# MSPBreakout.net
KiCad netlist of a schematic drawn in Altium Designer
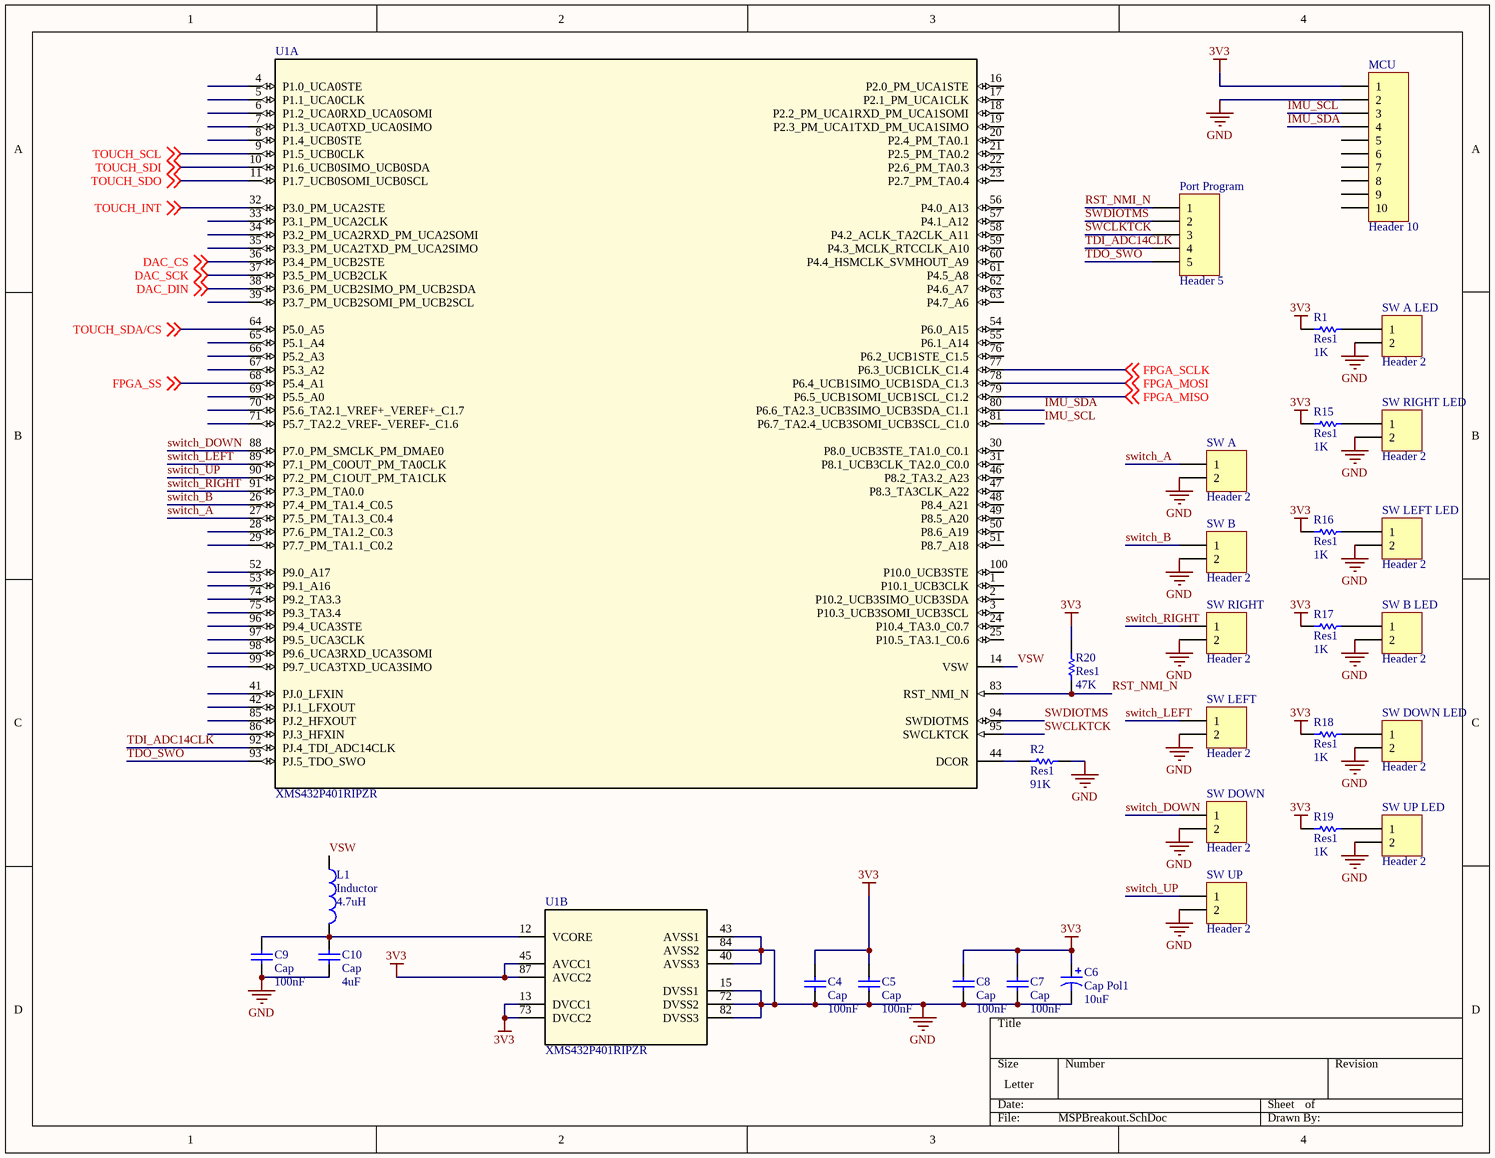
[diagram p0: MSPBreakout.SchDoc]

(export (version "E")
  (design (tool "Eeschema 10.0.6"))
  (components
    (comp (ref "C4")
      (value "Cap")
      (footprint "6-0805_M")
      (description "Capacitor")
      (fields (field (name "ALTIUM_VALUE") "100nF") (field (name "PUBLISHER") "Altium Limited"))
      (libsource (lib "Miscellaneous Devices") (part "Cap"))
    )
    (comp (ref "C5")
      (value "Cap")
      (footprint "6-0805_M")
      (description "Capacitor")
      (fields (field (name "ALTIUM_VALUE") "100nF") (field (name "PUBLISHER") "Altium Limited"))
      (libsource (lib "Miscellaneous Devices") (part "Cap"))
    )
    (comp (ref "C6")
      (value "Cap Pol1")
      (footprint "6-0805_M")
      (description "Polarized Capacitor (Radial)")
      (fields (field (name "ALTIUM_VALUE") "10uF") (field (name "PUBLISHER") "Altium Limited"))
      (libsource (lib "Miscellaneous Devices") (part "Cap Pol1"))
    )
    (comp (ref "C7")
      (value "Cap")
      (footprint "6-0805_M")
      (description "Capacitor")
      (fields (field (name "ALTIUM_VALUE") "100nF") (field (name "PUBLISHER") "Altium Limited"))
      (libsource (lib "Miscellaneous Devices") (part "Cap"))
    )
    (comp (ref "C8")
      (value "Cap")
      (footprint "6-0805_M")
      (description "Capacitor")
      (fields (field (name "ALTIUM_VALUE") "100nF") (field (name "PUBLISHER") "Altium Limited"))
      (libsource (lib "Miscellaneous Devices") (part "Cap"))
    )
    (comp (ref "C9")
      (value "Cap")
      (footprint "6-0805_M")
      (description "Capacitor")
      (fields (field (name "ALTIUM_VALUE") "100nF") (field (name "PUBLISHER") "Altium Limited"))
      (libsource (lib "Miscellaneous Devices") (part "Cap"))
    )
    (comp (ref "C10")
      (value "Cap")
      (footprint "6-0805_M")
      (description "Capacitor")
      (fields (field (name "ALTIUM_VALUE") "4uF") (field (name "PUBLISHER") "Altium Limited"))
      (libsource (lib "Miscellaneous Devices") (part "Cap"))
    )
    (comp (ref "L1")
      (value "Inductor")
      (footprint "AXIAL-0.3")
      (fields (field (name "ALTIUM_VALUE") "4.7uH") (field (name "PUBLISHER") "Altium Limited"))
      (libsource (lib "Miscellaneous Devices") (part "Inductor"))
    )
    (comp (ref "MCU")
      (value "Header 10")
      (footprint "HDR1X10")
      (description "Header, 10-Pin")
      (fields (field (name "PUBLISHER") "Altium Limited"))
      (libsource (lib "Miscellaneous Connectors") (part "Header 10"))
    )
    (comp (ref "Port Program")
      (value "Header 5")
      (footprint "HDR1X5")
      (description "Header, 5-Pin")
      (fields (field (name "PUBLISHER") "Altium Limited"))
      (libsource (lib "Miscellaneous Connectors") (part "Header 5"))
    )
    (comp (ref "R1")
      (value "Res1")
      (footprint "6-0805_M")
      (description "Resistor")
      (fields (field (name "ALTIUM_VALUE") "1K") (field (name "PUBLISHER") "Altium Limited"))
      (libsource (lib "Miscellaneous Devices") (part "Res1"))
    )
    (comp (ref "R2")
      (value "Res1")
      (footprint "6-0805_M")
      (description "Resistor")
      (fields (field (name "ALTIUM_VALUE") "91K") (field (name "PUBLISHER") "Altium Limited"))
      (libsource (lib "Miscellaneous Devices") (part "Res1"))
    )
    (comp (ref "R15")
      (value "Res1")
      (footprint "6-0805_M")
      (description "Resistor")
      (fields (field (name "ALTIUM_VALUE") "1K") (field (name "PUBLISHER") "Altium Limited"))
      (libsource (lib "Miscellaneous Devices") (part "Res1"))
    )
    (comp (ref "R16")
      (value "Res1")
      (footprint "6-0805_M")
      (description "Resistor")
      (fields (field (name "ALTIUM_VALUE") "1K") (field (name "PUBLISHER") "Altium Limited"))
      (libsource (lib "Miscellaneous Devices") (part "Res1"))
    )
    (comp (ref "R17")
      (value "Res1")
      (footprint "6-0805_M")
      (description "Resistor")
      (fields (field (name "ALTIUM_VALUE") "1K") (field (name "PUBLISHER") "Altium Limited"))
      (libsource (lib "Miscellaneous Devices") (part "Res1"))
    )
    (comp (ref "R18")
      (value "Res1")
      (footprint "6-0805_M")
      (description "Resistor")
      (fields (field (name "ALTIUM_VALUE") "1K") (field (name "PUBLISHER") "Altium Limited"))
      (libsource (lib "Miscellaneous Devices") (part "Res1"))
    )
    (comp (ref "R19")
      (value "Res1")
      (footprint "6-0805_M")
      (description "Resistor")
      (fields (field (name "ALTIUM_VALUE") "1K") (field (name "PUBLISHER") "Altium Limited"))
      (libsource (lib "Miscellaneous Devices") (part "Res1"))
    )
    (comp (ref "R20")
      (value "Res1")
      (footprint "6-0805_M")
      (description "Resistor")
      (fields (field (name "ALTIUM_VALUE") "47K") (field (name "PUBLISHER") "Altium Limited"))
      (libsource (lib "Miscellaneous Devices") (part "Res1"))
    )
    (comp (ref "SW A")
      (value "Header 2")
      (footprint "HDR1X2")
      (description "Header, 2-Pin")
      (fields (field (name "PUBLISHER") "Altium Limited"))
      (libsource (lib "Miscellaneous Connectors") (part "Header 2"))
    )
    (comp (ref "SW A LED")
      (value "Header 2")
      (footprint "HDR1X2")
      (description "Header, 2-Pin")
      (fields (field (name "PUBLISHER") "Altium Limited"))
      (libsource (lib "Miscellaneous Connectors") (part "Header 2"))
    )
    (comp (ref "SW B")
      (value "Header 2")
      (footprint "HDR1X2")
      (description "Header, 2-Pin")
      (fields (field (name "PUBLISHER") "Altium Limited"))
      (libsource (lib "Miscellaneous Connectors") (part "Header 2"))
    )
    (comp (ref "SW B LED")
      (value "Header 2")
      (footprint "HDR1X2")
      (description "Header, 2-Pin")
      (fields (field (name "PUBLISHER") "Altium Limited"))
      (libsource (lib "Miscellaneous Connectors") (part "Header 2"))
    )
    (comp (ref "SW DOWN")
      (value "Header 2")
      (footprint "HDR1X2")
      (description "Header, 2-Pin")
      (fields (field (name "PUBLISHER") "Altium Limited"))
      (libsource (lib "Miscellaneous Connectors") (part "Header 2"))
    )
    (comp (ref "SW DOWN LED")
      (value "Header 2")
      (footprint "HDR1X2")
      (description "Header, 2-Pin")
      (fields (field (name "PUBLISHER") "Altium Limited"))
      (libsource (lib "Miscellaneous Connectors") (part "Header 2"))
    )
    (comp (ref "SW LEFT")
      (value "Header 2")
      (footprint "HDR1X2")
      (description "Header, 2-Pin")
      (fields (field (name "PUBLISHER") "Altium Limited"))
      (libsource (lib "Miscellaneous Connectors") (part "Header 2"))
    )
    (comp (ref "SW LEFT LED")
      (value "Header 2")
      (footprint "HDR1X2")
      (description "Header, 2-Pin")
      (fields (field (name "PUBLISHER") "Altium Limited"))
      (libsource (lib "Miscellaneous Connectors") (part "Header 2"))
    )
    (comp (ref "SW RIGHT")
      (value "Header 2")
      (footprint "HDR1X2")
      (description "Header, 2-Pin")
      (fields (field (name "PUBLISHER") "Altium Limited"))
      (libsource (lib "Miscellaneous Connectors") (part "Header 2"))
    )
    (comp (ref "SW RIGHT LED")
      (value "Header 2")
      (footprint "HDR1X2")
      (description "Header, 2-Pin")
      (fields (field (name "PUBLISHER") "Altium Limited"))
      (libsource (lib "Miscellaneous Connectors") (part "Header 2"))
    )
    (comp (ref "SW UP")
      (value "Header 2")
      (footprint "HDR1X2")
      (description "Header, 2-Pin")
      (fields (field (name "PUBLISHER") "Altium Limited"))
      (libsource (lib "Miscellaneous Connectors") (part "Header 2"))
    )
    (comp (ref "SW UP LED")
      (value "Header 2")
      (footprint "HDR1X2")
      (description "Header, 2-Pin")
      (fields (field (name "PUBLISHER") "Altium Limited"))
      (libsource (lib "Miscellaneous Connectors") (part "Header 2"))
    )
    (comp (ref "U1")
      (value "XMS432P401RIPZR")
      (footprint "PZ0100A_M")
      (description "Imported")
      (fields (field (name "MANUFACTURER") "Texas Instruments"))
      (libsource (lib "2019-02-10_17-24-31") (part "XMS432P401RIPZR"))
    )
  )
  (nets
    (net (code "1") (name "/IMU_SCL") (class "Default")
      (node (ref "MCU") (pin "3") (pinfunction "3_3") (pintype "passive"))
      (node (ref "U1") (pin "81") (pinfunction "P6.7_TA2.4_UCB3SOMI_UCB3SCL_C1.0_81") (pintype "bidirectional"))
    )
    (net (code "2") (name "/IMU_SDA") (class "Default")
      (node (ref "MCU") (pin "4") (pinfunction "4_4") (pintype "passive"))
      (node (ref "U1") (pin "80") (pinfunction "P6.6_TA2.3_UCB3SIMO_UCB3SDA_C1.1_80") (pintype "bidirectional"))
    )
    (net (code "3") (name "/RST_NMI_N") (class "Default")
      (node (ref "Port Program") (pin "1") (pinfunction "1_1") (pintype "passive"))
      (node (ref "R20") (pin "1") (pinfunction "1_1") (pintype "passive"))
      (node (ref "U1") (pin "83") (pinfunction "RST_NMI_N_83") (pintype "input"))
    )
    (net (code "4") (name "/SWCLKTCK") (class "Default")
      (node (ref "Port Program") (pin "3") (pinfunction "3_3") (pintype "passive"))
      (node (ref "U1") (pin "95") (pinfunction "SWCLKTCK_95") (pintype "input"))
    )
    (net (code "5") (name "/SWDIOTMS") (class "Default")
      (node (ref "Port Program") (pin "2") (pinfunction "2_2") (pintype "passive"))
      (node (ref "U1") (pin "94") (pinfunction "SWDIOTMS_94") (pintype "bidirectional"))
    )
    (net (code "6") (name "/TDI_ADC14CLK") (class "Default")
      (node (ref "Port Program") (pin "4") (pinfunction "4_4") (pintype "passive"))
      (node (ref "U1") (pin "92") (pinfunction "PJ.4_TDI_ADC14CLK_92") (pintype "bidirectional"))
    )
    (net (code "7") (name "/TDO_SWO") (class "Default")
      (node (ref "Port Program") (pin "5") (pinfunction "5_5") (pintype "passive"))
      (node (ref "U1") (pin "93") (pinfunction "PJ.5_TDO_SWO_93") (pintype "bidirectional"))
    )
    (net (code "8") (name "/VSW") (class "Default")
      (node (ref "L1") (pin "1") (pinfunction "1_1") (pintype "passive"))
      (node (ref "U1") (pin "14") (pinfunction "VSW_14") (pintype "passive"))
    )
    (net (code "9") (name "/switch_A") (class "Default")
      (node (ref "SW A") (pin "1") (pinfunction "1_1") (pintype "passive"))
      (node (ref "U1") (pin "27") (pinfunction "P7.5_PM_TA1.3_C0.4_27") (pintype "bidirectional"))
    )
    (net (code "10") (name "/switch_B") (class "Default")
      (node (ref "SW B") (pin "1") (pinfunction "1_1") (pintype "passive"))
      (node (ref "U1") (pin "26") (pinfunction "P7.4_PM_TA1.4_C0.5_26") (pintype "bidirectional"))
    )
    (net (code "11") (name "/switch_DOWN") (class "Default")
      (node (ref "SW DOWN") (pin "1") (pinfunction "1_1") (pintype "passive"))
      (node (ref "U1") (pin "88") (pinfunction "P7.0_PM_SMCLK_PM_DMAE0_88") (pintype "bidirectional"))
    )
    (net (code "12") (name "/switch_LEFT") (class "Default")
      (node (ref "SW LEFT") (pin "1") (pinfunction "1_1") (pintype "passive"))
      (node (ref "U1") (pin "89") (pinfunction "P7.1_PM_C0OUT_PM_TA0CLK_89") (pintype "bidirectional"))
    )
    (net (code "13") (name "/switch_RIGHT") (class "Default")
      (node (ref "SW RIGHT") (pin "1") (pinfunction "1_1") (pintype "passive"))
      (node (ref "U1") (pin "91") (pinfunction "P7.3_PM_TA0.0_91") (pintype "bidirectional"))
    )
    (net (code "14") (name "/switch_UP") (class "Default")
      (node (ref "SW UP") (pin "1") (pinfunction "1_1") (pintype "passive"))
      (node (ref "U1") (pin "90") (pinfunction "P7.2_PM_C1OUT_PM_TA1CLK_90") (pintype "bidirectional"))
    )
    (net (code "15") (name "3V3") (class "Default")
      (node (ref "C4") (pin "2") (pinfunction "2_2") (pintype "passive"))
      (node (ref "C5") (pin "2") (pinfunction "2_2") (pintype "passive"))
      (node (ref "C6") (pin "1") (pinfunction "1_1") (pintype "passive"))
      (node (ref "C7") (pin "2") (pinfunction "2_2") (pintype "passive"))
      (node (ref "C8") (pin "2") (pinfunction "2_2") (pintype "passive"))
      (node (ref "MCU") (pin "1") (pinfunction "1_1") (pintype "passive"))
      (node (ref "R1") (pin "1") (pinfunction "1_1") (pintype "passive"))
      (node (ref "R15") (pin "1") (pinfunction "1_1") (pintype "passive"))
      (node (ref "R16") (pin "1") (pinfunction "1_1") (pintype "passive"))
      (node (ref "R17") (pin "1") (pinfunction "1_1") (pintype "passive"))
      (node (ref "R18") (pin "1") (pinfunction "1_1") (pintype "passive"))
      (node (ref "R19") (pin "1") (pinfunction "1_1") (pintype "passive"))
      (node (ref "R20") (pin "2") (pinfunction "2_2") (pintype "passive"))
      (node (ref "U1") (pin "13") (pinfunction "DVCC1_13") (pintype "power_in"))
      (node (ref "U1") (pin "45") (pinfunction "AVCC1_45") (pintype "power_in"))
      (node (ref "U1") (pin "73") (pinfunction "DVCC2_73") (pintype "power_in"))
      (node (ref "U1") (pin "87") (pinfunction "AVCC2_87") (pintype "power_in"))
    )
    (net (code "16") (name "DAC_CS") (class "Default")
      (node (ref "U1") (pin "36") (pinfunction "P3.4_PM_UCB2STE_36") (pintype "bidirectional"))
    )
    (net (code "17") (name "DAC_DIN") (class "Default")
      (node (ref "U1") (pin "38") (pinfunction "P3.6_PM_UCB2SIMO_PM_UCB2SDA_38") (pintype "bidirectional"))
    )
    (net (code "18") (name "DAC_SCK") (class "Default")
      (node (ref "U1") (pin "37") (pinfunction "P3.5_PM_UCB2CLK_37") (pintype "bidirectional"))
    )
    (net (code "19") (name "FPGA_MISO") (class "Default")
      (node (ref "U1") (pin "79") (pinfunction "P6.5_UCB1SOMI_UCB1SCL_C1.2_79") (pintype "bidirectional"))
    )
    (net (code "20") (name "FPGA_MOSI") (class "Default")
      (node (ref "U1") (pin "78") (pinfunction "P6.4_UCB1SIMO_UCB1SDA_C1.3_78") (pintype "bidirectional"))
    )
    (net (code "21") (name "FPGA_SCLK") (class "Default")
      (node (ref "U1") (pin "77") (pinfunction "P6.3_UCB1CLK_C1.4_77") (pintype "bidirectional"))
    )
    (net (code "22") (name "FPGA_SS") (class "Default")
      (node (ref "U1") (pin "68") (pinfunction "P5.4_A1_68") (pintype "bidirectional"))
    )
    (net (code "23") (name "GND") (class "Default")
      (node (ref "C10") (pin "1") (pinfunction "1_1") (pintype "passive"))
      (node (ref "C4") (pin "1") (pinfunction "1_1") (pintype "passive"))
      (node (ref "C5") (pin "1") (pinfunction "1_1") (pintype "passive"))
      (node (ref "C6") (pin "2") (pinfunction "2_2") (pintype "passive"))
      (node (ref "C7") (pin "1") (pinfunction "1_1") (pintype "passive"))
      (node (ref "C8") (pin "1") (pinfunction "1_1") (pintype "passive"))
      (node (ref "C9") (pin "1") (pinfunction "1_1") (pintype "passive"))
      (node (ref "MCU") (pin "2") (pinfunction "2_2") (pintype "passive"))
      (node (ref "R2") (pin "2") (pinfunction "2_2") (pintype "passive"))
      (node (ref "SW A") (pin "2") (pinfunction "2_2") (pintype "passive"))
      (node (ref "SW A LED") (pin "2") (pinfunction "2_2") (pintype "passive"))
      (node (ref "SW B") (pin "2") (pinfunction "2_2") (pintype "passive"))
      (node (ref "SW B LED") (pin "2") (pinfunction "2_2") (pintype "passive"))
      (node (ref "SW DOWN") (pin "2") (pinfunction "2_2") (pintype "passive"))
      (node (ref "SW DOWN LED") (pin "2") (pinfunction "2_2") (pintype "passive"))
      (node (ref "SW LEFT") (pin "2") (pinfunction "2_2") (pintype "passive"))
      (node (ref "SW LEFT LED") (pin "2") (pinfunction "2_2") (pintype "passive"))
      (node (ref "SW RIGHT") (pin "2") (pinfunction "2_2") (pintype "passive"))
      (node (ref "SW RIGHT LED") (pin "2") (pinfunction "2_2") (pintype "passive"))
      (node (ref "SW UP") (pin "2") (pinfunction "2_2") (pintype "passive"))
      (node (ref "SW UP LED") (pin "2") (pinfunction "2_2") (pintype "passive"))
      (node (ref "U1") (pin "15") (pinfunction "DVSS1_15") (pintype "power_in"))
      (node (ref "U1") (pin "40") (pinfunction "AVSS3_40") (pintype "power_in"))
      (node (ref "U1") (pin "43") (pinfunction "AVSS1_43") (pintype "power_in"))
      (node (ref "U1") (pin "72") (pinfunction "DVSS2_72") (pintype "power_in"))
      (node (ref "U1") (pin "82") (pinfunction "DVSS3_82") (pintype "power_in"))
      (node (ref "U1") (pin "84") (pinfunction "AVSS2_84") (pintype "power_in"))
    )
    (net (code "24") (name "Net-(R1-Pad2)") (class "Default")
      (node (ref "R1") (pin "2") (pinfunction "2_2") (pintype "passive"))
      (node (ref "SW A LED") (pin "1") (pinfunction "1_1") (pintype "passive"))
    )
    (net (code "25") (name "Net-(R15-Pad2)") (class "Default")
      (node (ref "R15") (pin "2") (pinfunction "2_2") (pintype "passive"))
      (node (ref "SW RIGHT LED") (pin "1") (pinfunction "1_1") (pintype "passive"))
    )
    (net (code "26") (name "Net-(R16-Pad2)") (class "Default")
      (node (ref "R16") (pin "2") (pinfunction "2_2") (pintype "passive"))
      (node (ref "SW LEFT LED") (pin "1") (pinfunction "1_1") (pintype "passive"))
    )
    (net (code "27") (name "Net-(R17-Pad2)") (class "Default")
      (node (ref "R17") (pin "2") (pinfunction "2_2") (pintype "passive"))
      (node (ref "SW B LED") (pin "1") (pinfunction "1_1") (pintype "passive"))
    )
    (net (code "28") (name "Net-(R18-Pad2)") (class "Default")
      (node (ref "R18") (pin "2") (pinfunction "2_2") (pintype "passive"))
      (node (ref "SW DOWN LED") (pin "1") (pinfunction "1_1") (pintype "passive"))
    )
    (net (code "29") (name "Net-(R19-Pad2)") (class "Default")
      (node (ref "R19") (pin "2") (pinfunction "2_2") (pintype "passive"))
      (node (ref "SW UP LED") (pin "1") (pinfunction "1_1") (pintype "passive"))
    )
    (net (code "30") (name "Net-(U1A-DCOR)") (class "Default")
      (node (ref "R2") (pin "1") (pinfunction "1_1") (pintype "passive"))
      (node (ref "U1") (pin "44") (pinfunction "DCOR_44") (pintype "passive"))
    )
    (net (code "31") (name "Net-(U1B-VCORE)") (class "Default")
      (node (ref "C10") (pin "2") (pinfunction "2_2") (pintype "passive"))
      (node (ref "C9") (pin "2") (pinfunction "2_2") (pintype "passive"))
      (node (ref "L1") (pin "2") (pinfunction "2_2") (pintype "passive"))
      (node (ref "U1") (pin "12") (pinfunction "VCORE_12") (pintype "power_in"))
    )
    (net (code "32") (name "TOUCH_INT") (class "Default")
      (node (ref "U1") (pin "32") (pinfunction "P3.0_PM_UCA2STE_32") (pintype "bidirectional"))
    )
    (net (code "33") (name "TOUCH_SCL") (class "Default")
      (node (ref "U1") (pin "9") (pinfunction "P1.5_UCB0CLK_9") (pintype "bidirectional"))
    )
    (net (code "34") (name "TOUCH_SDA{slash}CS") (class "Default")
      (node (ref "U1") (pin "64") (pinfunction "P5.0_A5_64") (pintype "bidirectional"))
    )
    (net (code "35") (name "TOUCH_SDI") (class "Default")
      (node (ref "U1") (pin "10") (pinfunction "P1.6_UCB0SIMO_UCB0SDA_10") (pintype "bidirectional"))
    )
    (net (code "36") (name "TOUCH_SDO") (class "Default")
      (node (ref "U1") (pin "11") (pinfunction "P1.7_UCB0SOMI_UCB0SCL_11") (pintype "bidirectional"))
    )
    (net (code "37") (name "unconnected-(MCU-Pad5)") (class "Default")
      (node (ref "MCU") (pin "5") (pinfunction "5_5") (pintype "passive"))
    )
    (net (code "38") (name "unconnected-(MCU-Pad6)") (class "Default")
      (node (ref "MCU") (pin "6") (pinfunction "6_6") (pintype "passive"))
    )
    (net (code "39") (name "unconnected-(MCU-Pad7)") (class "Default")
      (node (ref "MCU") (pin "7") (pinfunction "7_7") (pintype "passive"))
    )
    (net (code "40") (name "unconnected-(MCU-Pad8)") (class "Default")
      (node (ref "MCU") (pin "8") (pinfunction "8_8") (pintype "passive"))
    )
    (net (code "41") (name "unconnected-(MCU-Pad9)") (class "Default")
      (node (ref "MCU") (pin "9") (pinfunction "9_9") (pintype "passive"))
    )
    (net (code "42") (name "unconnected-(MCU-Pad10)") (class "Default")
      (node (ref "MCU") (pin "10") (pinfunction "10_10") (pintype "passive"))
    )
    (net (code "43") (name "unconnected-(U1A-P1.0_UCA0STE-Pad4)") (class "Default")
      (node (ref "U1") (pin "4") (pinfunction "P1.0_UCA0STE_4") (pintype "bidirectional"))
    )
    (net (code "44") (name "unconnected-(U1A-P1.1_UCA0CLK-Pad5)") (class "Default")
      (node (ref "U1") (pin "5") (pinfunction "P1.1_UCA0CLK_5") (pintype "bidirectional"))
    )
    (net (code "45") (name "unconnected-(U1A-P1.2_UCA0RXD_UCA0SOMI-Pad6)") (class "Default")
      (node (ref "U1") (pin "6") (pinfunction "P1.2_UCA0RXD_UCA0SOMI_6") (pintype "bidirectional"))
    )
    (net (code "46") (name "unconnected-(U1A-P1.3_UCA0TXD_UCA0SIMO-Pad7)") (class "Default")
      (node (ref "U1") (pin "7") (pinfunction "P1.3_UCA0TXD_UCA0SIMO_7") (pintype "bidirectional"))
    )
    (net (code "47") (name "unconnected-(U1A-P1.4_UCB0STE-Pad8)") (class "Default")
      (node (ref "U1") (pin "8") (pinfunction "P1.4_UCB0STE_8") (pintype "bidirectional"))
    )
    (net (code "48") (name "unconnected-(U1A-P2.0_PM_UCA1STE-Pad16)") (class "Default")
      (node (ref "U1") (pin "16") (pinfunction "P2.0_PM_UCA1STE_16") (pintype "bidirectional"))
    )
    (net (code "49") (name "unconnected-(U1A-P2.1_PM_UCA1CLK-Pad17)") (class "Default")
      (node (ref "U1") (pin "17") (pinfunction "P2.1_PM_UCA1CLK_17") (pintype "bidirectional"))
    )
    (net (code "50") (name "unconnected-(U1A-P2.2_PM_UCA1RXD_PM_UCA1SOMI-Pad18)") (class "Default")
      (node (ref "U1") (pin "18") (pinfunction "P2.2_PM_UCA1RXD_PM_UCA1SOMI_18") (pintype "bidirectional"))
    )
    (net (code "51") (name "unconnected-(U1A-P2.3_PM_UCA1TXD_PM_UCA1SIMO-Pad19)") (class "Default")
      (node (ref "U1") (pin "19") (pinfunction "P2.3_PM_UCA1TXD_PM_UCA1SIMO_19") (pintype "bidirectional"))
    )
    (net (code "52") (name "unconnected-(U1A-P2.4_PM_TA0.1-Pad20)") (class "Default")
      (node (ref "U1") (pin "20") (pinfunction "P2.4_PM_TA0.1_20") (pintype "bidirectional"))
    )
    (net (code "53") (name "unconnected-(U1A-P2.5_PM_TA0.2-Pad21)") (class "Default")
      (node (ref "U1") (pin "21") (pinfunction "P2.5_PM_TA0.2_21") (pintype "bidirectional"))
    )
    (net (code "54") (name "unconnected-(U1A-P2.6_PM_TA0.3-Pad22)") (class "Default")
      (node (ref "U1") (pin "22") (pinfunction "P2.6_PM_TA0.3_22") (pintype "bidirectional"))
    )
    (net (code "55") (name "unconnected-(U1A-P2.7_PM_TA0.4-Pad23)") (class "Default")
      (node (ref "U1") (pin "23") (pinfunction "P2.7_PM_TA0.4_23") (pintype "bidirectional"))
    )
    (net (code "56") (name "unconnected-(U1A-P3.1_PM_UCA2CLK-Pad33)") (class "Default")
      (node (ref "U1") (pin "33") (pinfunction "P3.1_PM_UCA2CLK_33") (pintype "bidirectional"))
    )
    (net (code "57") (name "unconnected-(U1A-P3.2_PM_UCA2RXD_PM_UCA2SOMI-Pad34)") (class "Default")
      (node (ref "U1") (pin "34") (pinfunction "P3.2_PM_UCA2RXD_PM_UCA2SOMI_34") (pintype "bidirectional"))
    )
    (net (code "58") (name "unconnected-(U1A-P3.3_PM_UCA2TXD_PM_UCA2SIMO-Pad35)") (class "Default")
      (node (ref "U1") (pin "35") (pinfunction "P3.3_PM_UCA2TXD_PM_UCA2SIMO_35") (pintype "bidirectional"))
    )
    (net (code "59") (name "unconnected-(U1A-P3.7_PM_UCB2SOMI_PM_UCB2SCL-Pad39)") (class "Default")
      (node (ref "U1") (pin "39") (pinfunction "P3.7_PM_UCB2SOMI_PM_UCB2SCL_39") (pintype "bidirectional"))
    )
    (net (code "60") (name "unconnected-(U1A-P4.0_A13-Pad56)") (class "Default")
      (node (ref "U1") (pin "56") (pinfunction "P4.0_A13_56") (pintype "bidirectional"))
    )
    (net (code "61") (name "unconnected-(U1A-P4.1_A12-Pad57)") (class "Default")
      (node (ref "U1") (pin "57") (pinfunction "P4.1_A12_57") (pintype "bidirectional"))
    )
    (net (code "62") (name "unconnected-(U1A-P4.2_ACLK_TA2CLK_A11-Pad58)") (class "Default")
      (node (ref "U1") (pin "58") (pinfunction "P4.2_ACLK_TA2CLK_A11_58") (pintype "bidirectional"))
    )
    (net (code "63") (name "unconnected-(U1A-P4.3_MCLK_RTCCLK_A10-Pad59)") (class "Default")
      (node (ref "U1") (pin "59") (pinfunction "P4.3_MCLK_RTCCLK_A10_59") (pintype "bidirectional"))
    )
    (net (code "64") (name "unconnected-(U1A-P4.4_HSMCLK_SVMHOUT_A9-Pad60)") (class "Default")
      (node (ref "U1") (pin "60") (pinfunction "P4.4_HSMCLK_SVMHOUT_A9_60") (pintype "bidirectional"))
    )
    (net (code "65") (name "unconnected-(U1A-P4.5_A8-Pad61)") (class "Default")
      (node (ref "U1") (pin "61") (pinfunction "P4.5_A8_61") (pintype "bidirectional"))
    )
    (net (code "66") (name "unconnected-(U1A-P4.6_A7-Pad62)") (class "Default")
      (node (ref "U1") (pin "62") (pinfunction "P4.6_A7_62") (pintype "bidirectional"))
    )
    (net (code "67") (name "unconnected-(U1A-P4.7_A6-Pad63)") (class "Default")
      (node (ref "U1") (pin "63") (pinfunction "P4.7_A6_63") (pintype "bidirectional"))
    )
    (net (code "68") (name "unconnected-(U1A-P5.1_A4-Pad65)") (class "Default")
      (node (ref "U1") (pin "65") (pinfunction "P5.1_A4_65") (pintype "bidirectional"))
    )
    (net (code "69") (name "unconnected-(U1A-P5.2_A3-Pad66)") (class "Default")
      (node (ref "U1") (pin "66") (pinfunction "P5.2_A3_66") (pintype "bidirectional"))
    )
    (net (code "70") (name "unconnected-(U1A-P5.3_A2-Pad67)") (class "Default")
      (node (ref "U1") (pin "67") (pinfunction "P5.3_A2_67") (pintype "bidirectional"))
    )
    (net (code "71") (name "unconnected-(U1A-P5.5_A0-Pad69)") (class "Default")
      (node (ref "U1") (pin "69") (pinfunction "P5.5_A0_69") (pintype "bidirectional"))
    )
    (net (code "72") (name "unconnected-(U1A-P5.6_TA2.1_VREF+_VEREF+_C1.7-Pad70)") (class "Default")
      (node (ref "U1") (pin "70") (pinfunction "P5.6_TA2.1_VREF+_VEREF+_C1.7_70") (pintype "bidirectional"))
    )
    (net (code "73") (name "unconnected-(U1A-P5.7_TA2.2_VREF-_VEREF-_C1.6-Pad71)") (class "Default")
      (node (ref "U1") (pin "71") (pinfunction "P5.7_TA2.2_VREF-_VEREF-_C1.6_71") (pintype "bidirectional"))
    )
    (net (code "74") (name "unconnected-(U1A-P6.0_A15-Pad54)") (class "Default")
      (node (ref "U1") (pin "54") (pinfunction "P6.0_A15_54") (pintype "bidirectional"))
    )
    (net (code "75") (name "unconnected-(U1A-P6.1_A14-Pad55)") (class "Default")
      (node (ref "U1") (pin "55") (pinfunction "P6.1_A14_55") (pintype "bidirectional"))
    )
    (net (code "76") (name "unconnected-(U1A-P6.2_UCB1STE_C1.5-Pad76)") (class "Default")
      (node (ref "U1") (pin "76") (pinfunction "P6.2_UCB1STE_C1.5_76") (pintype "bidirectional"))
    )
    (net (code "77") (name "unconnected-(U1A-P7.6_PM_TA1.2_C0.3-Pad28)") (class "Default")
      (node (ref "U1") (pin "28") (pinfunction "P7.6_PM_TA1.2_C0.3_28") (pintype "bidirectional"))
    )
    (net (code "78") (name "unconnected-(U1A-P7.7_PM_TA1.1_C0.2-Pad29)") (class "Default")
      (node (ref "U1") (pin "29") (pinfunction "P7.7_PM_TA1.1_C0.2_29") (pintype "bidirectional"))
    )
    (net (code "79") (name "unconnected-(U1A-P8.0_UCB3STE_TA1.0_C0.1-Pad30)") (class "Default")
      (node (ref "U1") (pin "30") (pinfunction "P8.0_UCB3STE_TA1.0_C0.1_30") (pintype "bidirectional"))
    )
    (net (code "80") (name "unconnected-(U1A-P8.1_UCB3CLK_TA2.0_C0.0-Pad31)") (class "Default")
      (node (ref "U1") (pin "31") (pinfunction "P8.1_UCB3CLK_TA2.0_C0.0_31") (pintype "bidirectional"))
    )
    (net (code "81") (name "unconnected-(U1A-P8.2_TA3.2_A23-Pad46)") (class "Default")
      (node (ref "U1") (pin "46") (pinfunction "P8.2_TA3.2_A23_46") (pintype "bidirectional"))
    )
    (net (code "82") (name "unconnected-(U1A-P8.3_TA3CLK_A22-Pad47)") (class "Default")
      (node (ref "U1") (pin "47") (pinfunction "P8.3_TA3CLK_A22_47") (pintype "bidirectional"))
    )
    (net (code "83") (name "unconnected-(U1A-P8.4_A21-Pad48)") (class "Default")
      (node (ref "U1") (pin "48") (pinfunction "P8.4_A21_48") (pintype "bidirectional"))
    )
    (net (code "84") (name "unconnected-(U1A-P8.5_A20-Pad49)") (class "Default")
      (node (ref "U1") (pin "49") (pinfunction "P8.5_A20_49") (pintype "bidirectional"))
    )
    (net (code "85") (name "unconnected-(U1A-P8.6_A19-Pad50)") (class "Default")
      (node (ref "U1") (pin "50") (pinfunction "P8.6_A19_50") (pintype "bidirectional"))
    )
    (net (code "86") (name "unconnected-(U1A-P8.7_A18-Pad51)") (class "Default")
      (node (ref "U1") (pin "51") (pinfunction "P8.7_A18_51") (pintype "bidirectional"))
    )
    (net (code "87") (name "unconnected-(U1A-P9.0_A17-Pad52)") (class "Default")
      (node (ref "U1") (pin "52") (pinfunction "P9.0_A17_52") (pintype "bidirectional"))
    )
    (net (code "88") (name "unconnected-(U1A-P9.1_A16-Pad53)") (class "Default")
      (node (ref "U1") (pin "53") (pinfunction "P9.1_A16_53") (pintype "bidirectional"))
    )
    (net (code "89") (name "unconnected-(U1A-P9.2_TA3.3-Pad74)") (class "Default")
      (node (ref "U1") (pin "74") (pinfunction "P9.2_TA3.3_74") (pintype "bidirectional"))
    )
    (net (code "90") (name "unconnected-(U1A-P9.3_TA3.4-Pad75)") (class "Default")
      (node (ref "U1") (pin "75") (pinfunction "P9.3_TA3.4_75") (pintype "bidirectional"))
    )
    (net (code "91") (name "unconnected-(U1A-P9.4_UCA3STE-Pad96)") (class "Default")
      (node (ref "U1") (pin "96") (pinfunction "P9.4_UCA3STE_96") (pintype "bidirectional"))
    )
    (net (code "92") (name "unconnected-(U1A-P9.5_UCA3CLK-Pad97)") (class "Default")
      (node (ref "U1") (pin "97") (pinfunction "P9.5_UCA3CLK_97") (pintype "bidirectional"))
    )
    (net (code "93") (name "unconnected-(U1A-P9.6_UCA3RXD_UCA3SOMI-Pad98)") (class "Default")
      (node (ref "U1") (pin "98") (pinfunction "P9.6_UCA3RXD_UCA3SOMI_98") (pintype "bidirectional"))
    )
    (net (code "94") (name "unconnected-(U1A-P9.7_UCA3TXD_UCA3SIMO-Pad99)") (class "Default")
      (node (ref "U1") (pin "99") (pinfunction "P9.7_UCA3TXD_UCA3SIMO_99") (pintype "bidirectional"))
    )
    (net (code "95") (name "unconnected-(U1A-P10.0_UCB3STE-Pad100)") (class "Default")
      (node (ref "U1") (pin "100") (pinfunction "P10.0_UCB3STE_100") (pintype "bidirectional"))
    )
    (net (code "96") (name "unconnected-(U1A-P10.1_UCB3CLK-Pad1)") (class "Default")
      (node (ref "U1") (pin "1") (pinfunction "P10.1_UCB3CLK_1") (pintype "bidirectional"))
    )
    (net (code "97") (name "unconnected-(U1A-P10.2_UCB3SIMO_UCB3SDA-Pad2)") (class "Default")
      (node (ref "U1") (pin "2") (pinfunction "P10.2_UCB3SIMO_UCB3SDA_2") (pintype "bidirectional"))
    )
    (net (code "98") (name "unconnected-(U1A-P10.3_UCB3SOMI_UCB3SCL-Pad3)") (class "Default")
      (node (ref "U1") (pin "3") (pinfunction "P10.3_UCB3SOMI_UCB3SCL_3") (pintype "bidirectional"))
    )
    (net (code "99") (name "unconnected-(U1A-P10.4_TA3.0_C0.7-Pad24)") (class "Default")
      (node (ref "U1") (pin "24") (pinfunction "P10.4_TA3.0_C0.7_24") (pintype "bidirectional"))
    )
    (net (code "100") (name "unconnected-(U1A-P10.5_TA3.1_C0.6-Pad25)") (class "Default")
      (node (ref "U1") (pin "25") (pinfunction "P10.5_TA3.1_C0.6_25") (pintype "bidirectional"))
    )
    (net (code "101") (name "unconnected-(U1A-PJ.0_LFXIN-Pad41)") (class "Default")
      (node (ref "U1") (pin "41") (pinfunction "PJ.0_LFXIN_41") (pintype "bidirectional"))
    )
    (net (code "102") (name "unconnected-(U1A-PJ.1_LFXOUT-Pad42)") (class "Default")
      (node (ref "U1") (pin "42") (pinfunction "PJ.1_LFXOUT_42") (pintype "bidirectional"))
    )
    (net (code "103") (name "unconnected-(U1A-PJ.2_HFXOUT-Pad85)") (class "Default")
      (node (ref "U1") (pin "85") (pinfunction "PJ.2_HFXOUT_85") (pintype "bidirectional"))
    )
    (net (code "104") (name "unconnected-(U1A-PJ.3_HFXIN-Pad86)") (class "Default")
      (node (ref "U1") (pin "86") (pinfunction "PJ.3_HFXIN_86") (pintype "bidirectional"))
    )
  )
)
